# H08R6.net
KiCad netlist of a schematic drawn in EAGLE
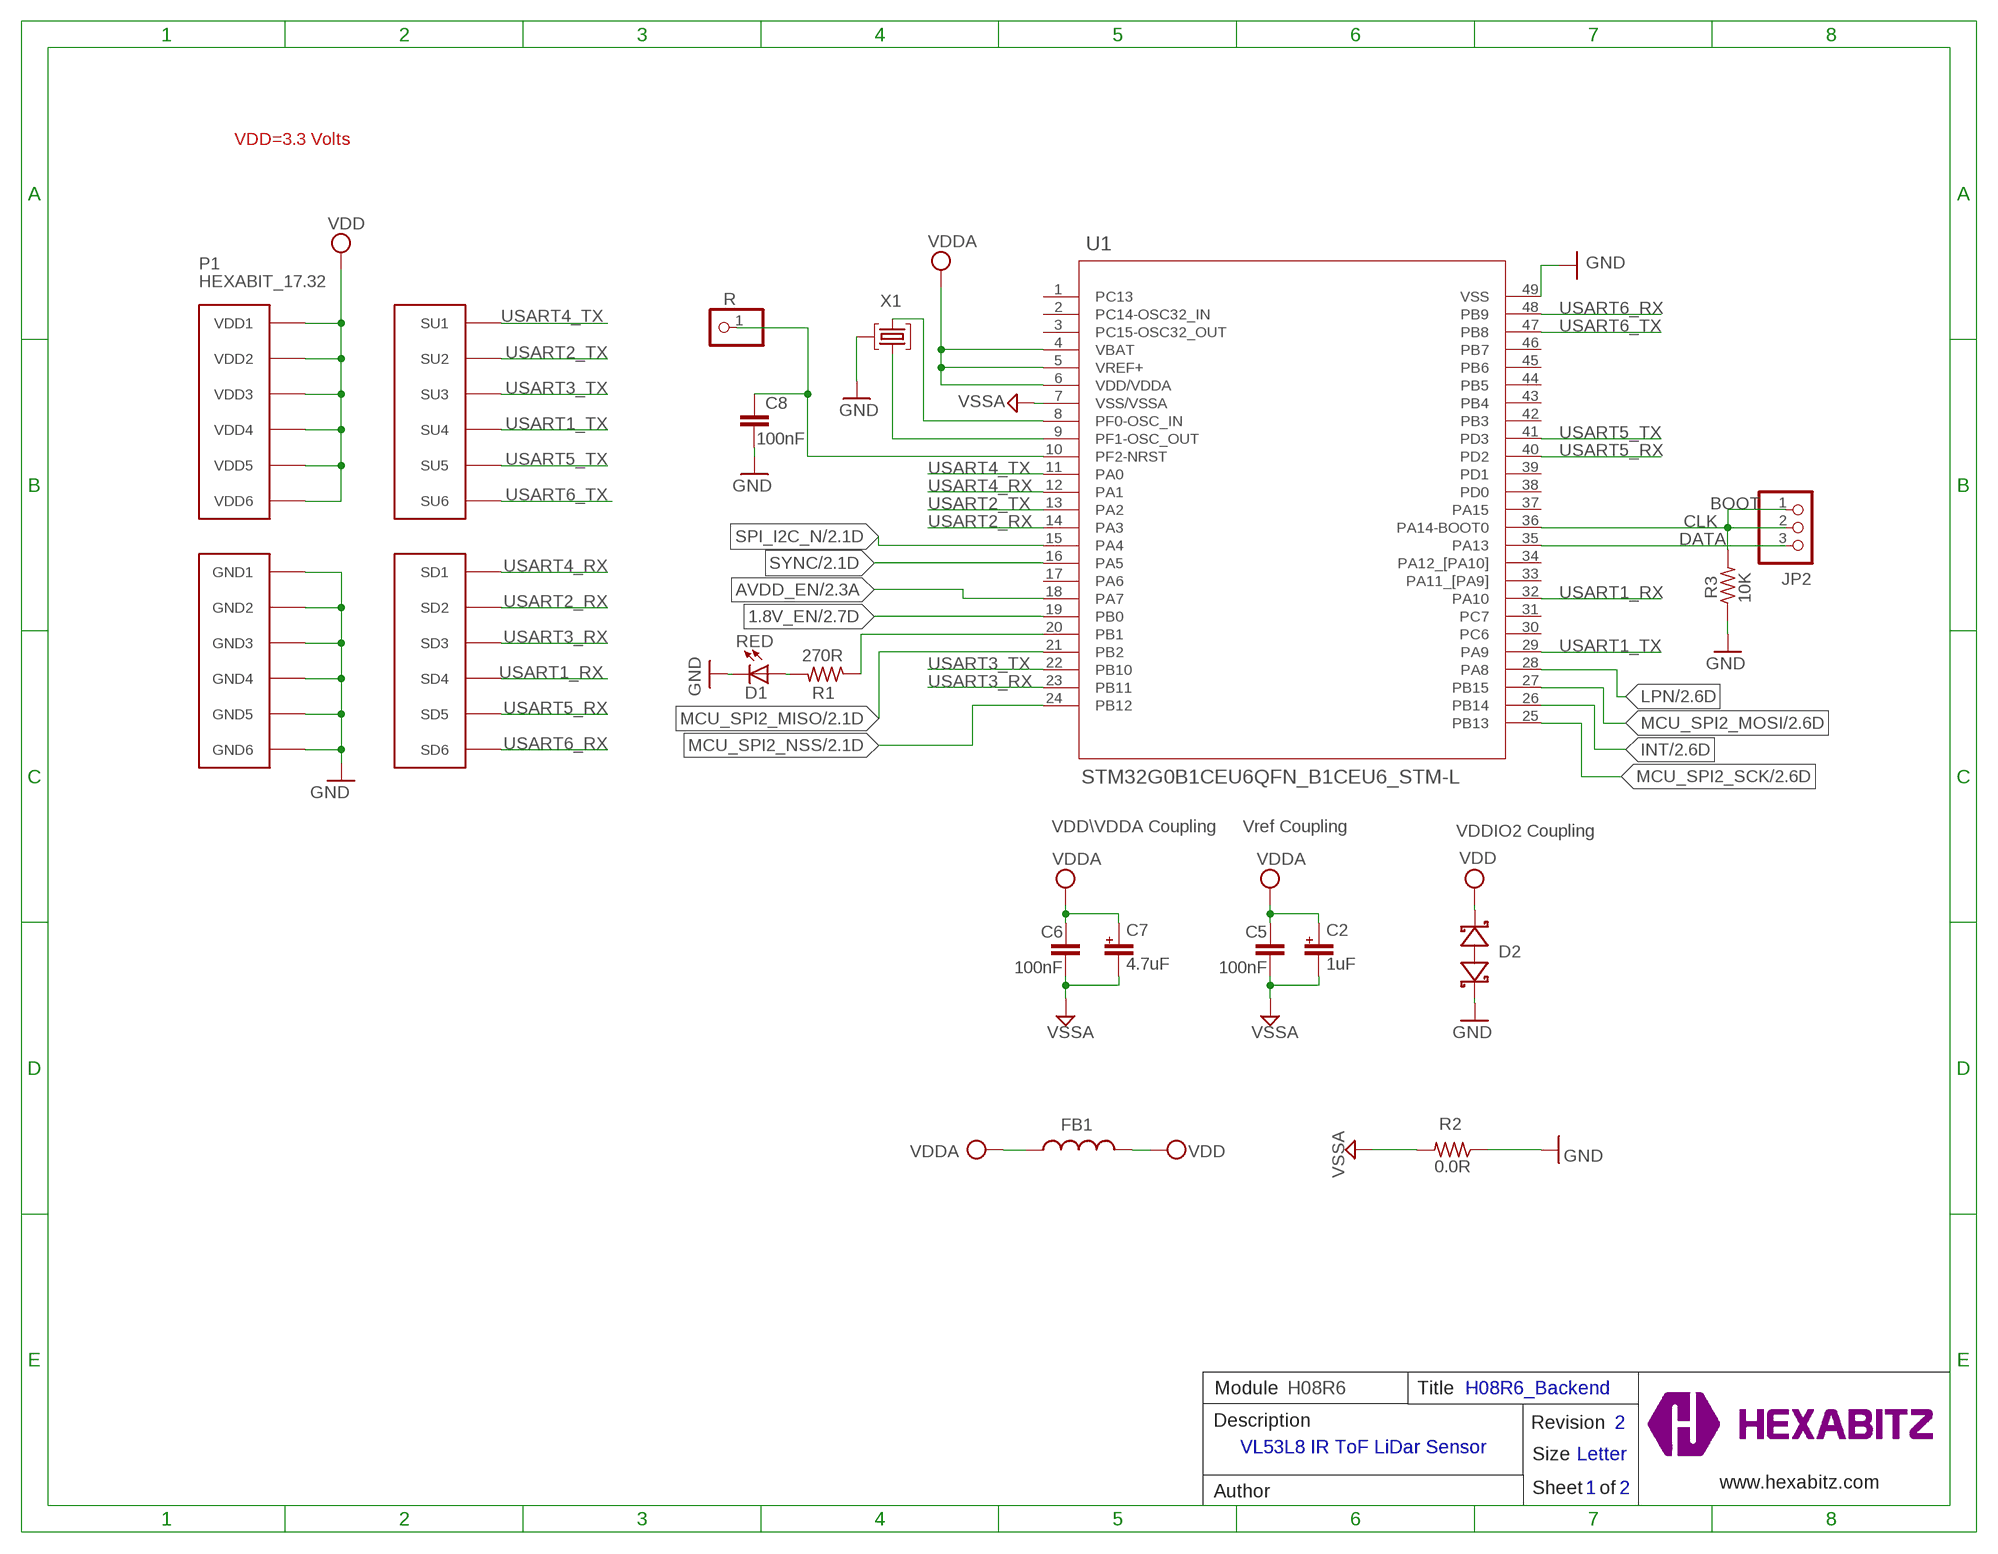
[diagram p0: schematic, sheet 1]
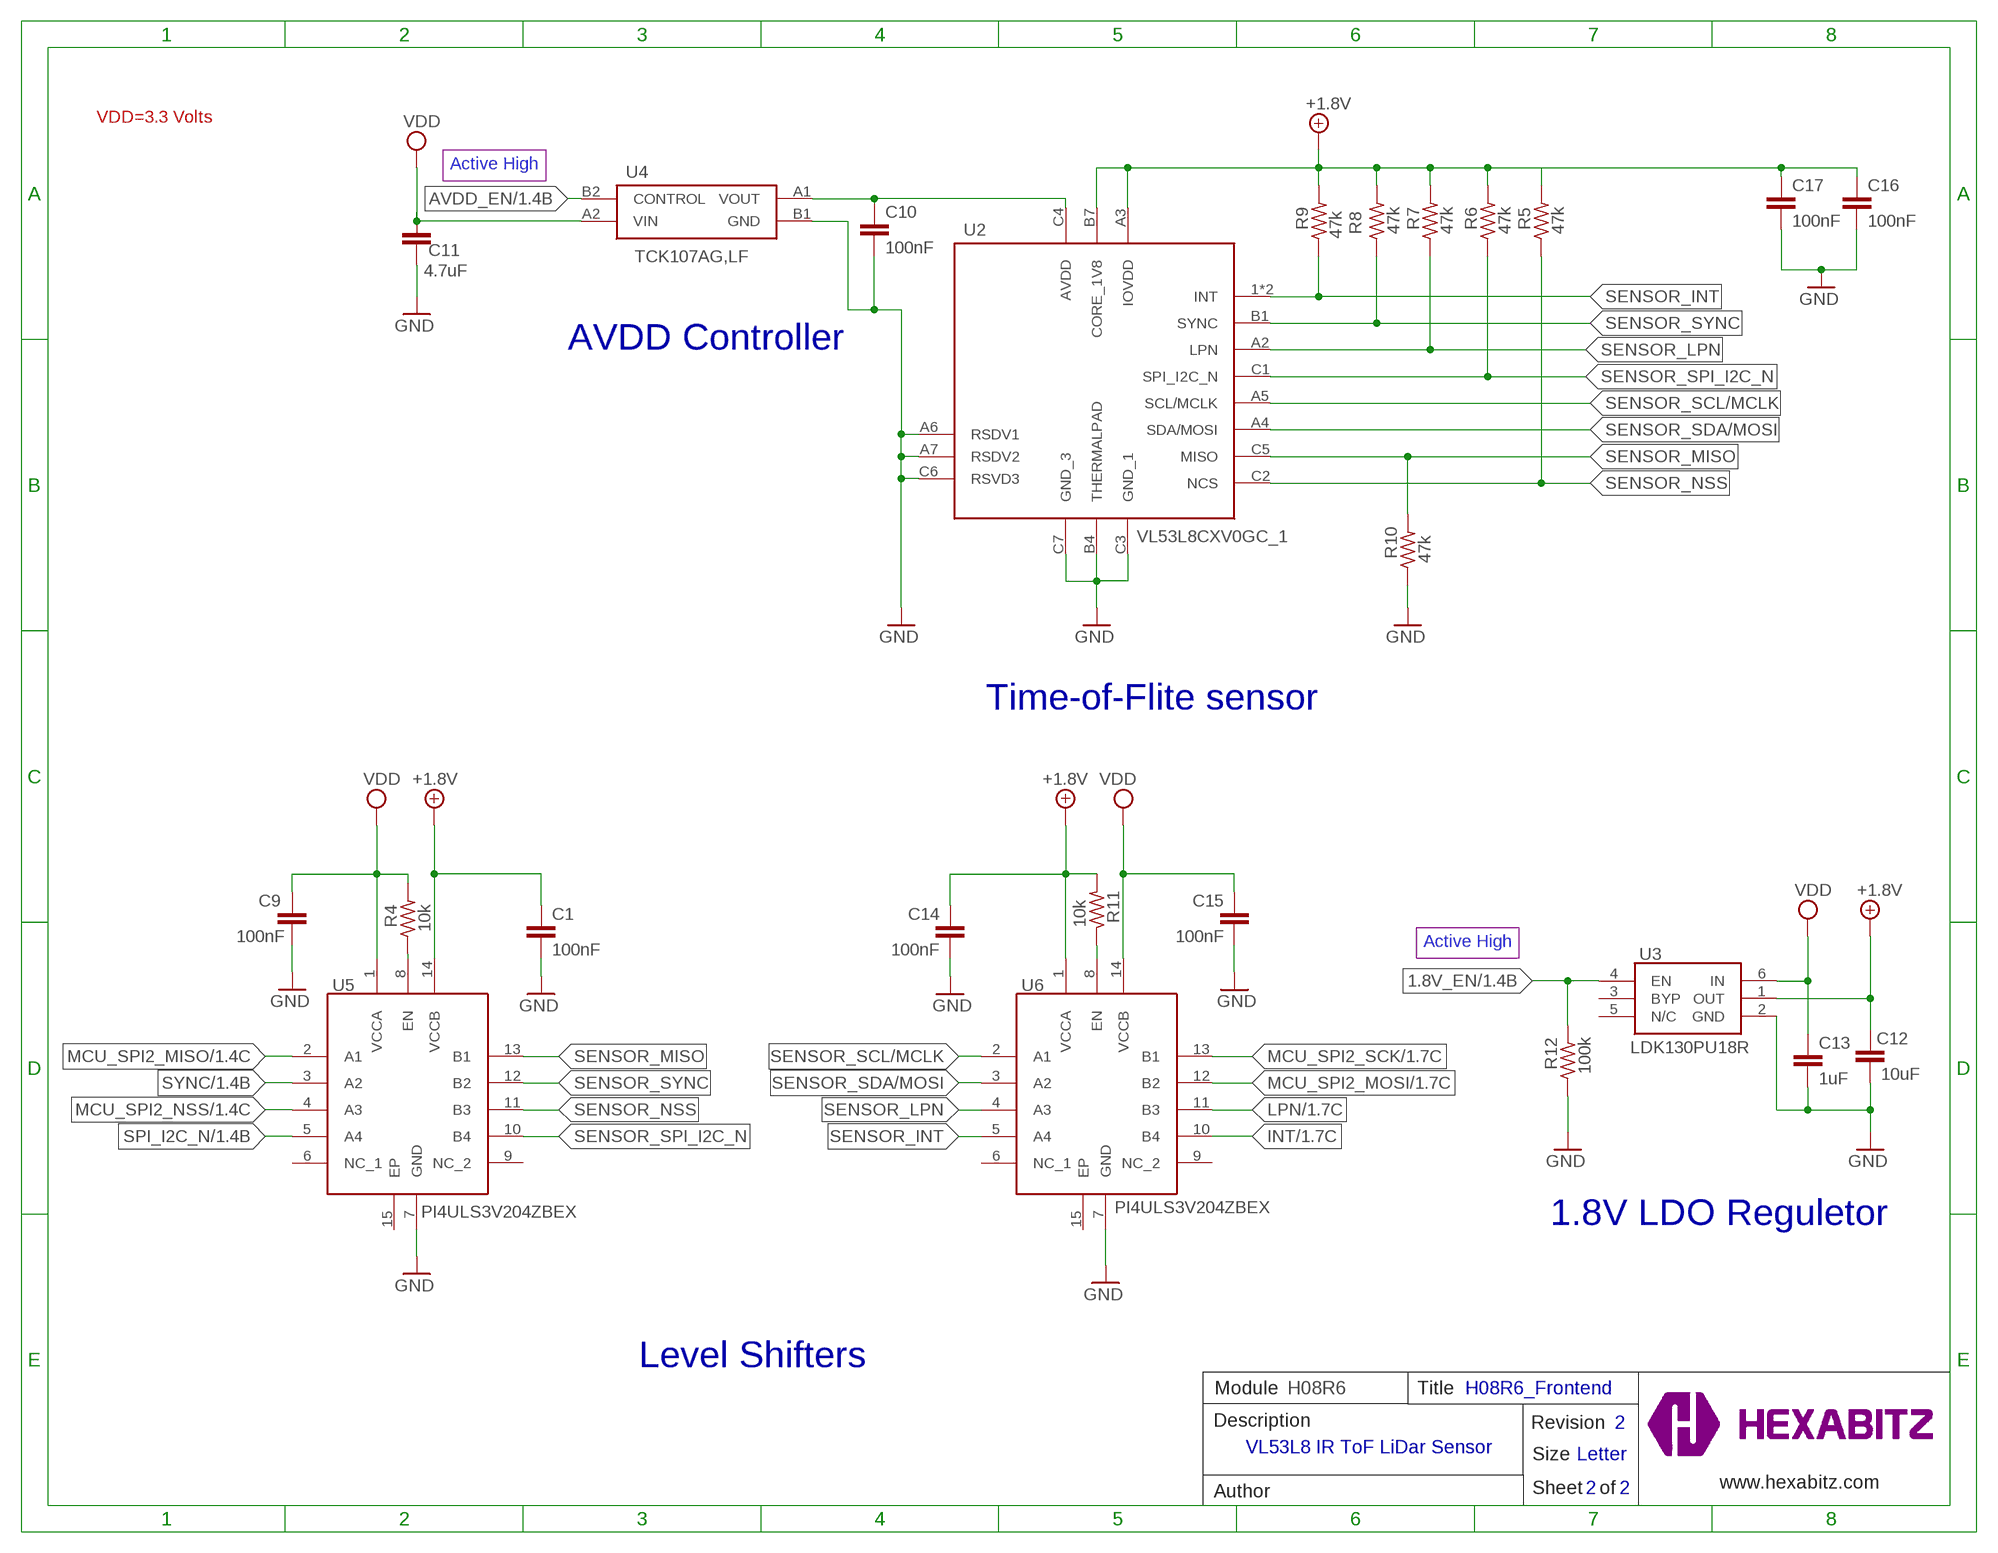
[diagram p1: schematic, sheet 2]

(export (version "E")
  (design (tool "Eeschema 10.0.6"))
  (components
    (comp (ref "C2")
      (value "1uF")
      (footprint "eagle-import:C-0603-POL")
      (libsource (lib "eagle-import") (part "C-0603-POL"))
    )
    (comp (ref "C5")
      (value "100nF")
      (footprint "eagle-import:C-0402")
      (libsource (lib "eagle-import") (part "C-0402"))
    )
    (comp (ref "C6")
      (value "100nF")
      (footprint "eagle-import:C-0402")
      (libsource (lib "eagle-import") (part "C-0402"))
    )
    (comp (ref "C7")
      (value "4.7uF")
      (footprint "eagle-import:C-0603-POL")
      (libsource (lib "eagle-import") (part "C-0603-POL"))
    )
    (comp (ref "C8")
      (value "100nF")
      (footprint "eagle-import:C-0402")
      (libsource (lib "eagle-import") (part "C-0402"))
    )
    (comp (ref "D1")
      (value "RED")
      (footprint "eagle-import:VLMS1300-GS08")
      (fields
        (field (name "MPN") "VLMS1300-GS08")
        (field (name "MFN") "Vishay")
        (field (name "MPN_1") "VLMS1300-GS08")
        (field (name "OCTOPART_URL") "https://octopart.com/vlms1300-gs08-vishay-21709201?r=sp&s=_gcP4_q8T1SC6PJQPTQ9yA")
      )
      (libsource (lib "eagle-import") (part "VLMS1300-GS08"))
    )
    (comp (ref "D2")
      (value "BOURNS_CDSOD323-T03SCBOURNS_CDSOD323-T03SC_0_0")
      (footprint "eagle-import:BOURNS_CDSOD323-T03SC_0")
      (fields (field (name "MPN") "CDSOD323-T03SC"))
      (libsource (lib "eagle-import") (part "BOURNS_CDSOD323-T03SCBOURNS_CDSOD323-T03SC_0_0"))
    )
    (comp (ref "FB1")
      (value "FB-TDK_MMZ1608Y300B")
      (footprint "eagle-import:FB-TDK_MMZ1608Y300B")
      (fields
        (field (name "MFN") "TDK ")
        (field (name "MPN") "MMZ1608Y300B")
        (field (name "OCTOPART_URL") "https://octopart.com/mmz1608y300b-tdk-368280?r=sp&s=cd9_2ZEqQ9q9UNBuQgHAiA")
      )
      (libsource (lib "eagle-import") (part "FB-TDK_MMZ1608Y300B"))
    )
    (comp (ref "JP2")
      (value "PINHD-1X3")
      (footprint "eagle-import:1X03")
      (libsource (lib "eagle-import") (part "PINHD-1X3"))
    )
    (comp (ref "P1")
      (value "HEXABIT_17.32")
      (footprint "eagle-import:HEXABIT_17.32")
      (libsource (lib "eagle-import") (part "HEXABIT_?17.32"))
    )
    (comp (ref "R")
      (value "R")
      (footprint "eagle-import:1X01")
      (fields (field (name "MPN") "87227-1"))
      (libsource (lib "eagle-import") (part "PINHD-1X1"))
    )
    (comp (ref "R1")
      (value "270R")
      (footprint "eagle-import:R-0402")
      (libsource (lib "eagle-import") (part "R-0402"))
    )
    (comp (ref "R2")
      (value "0.0R")
      (footprint "eagle-import:R-0402")
      (fields
        (field (name "MFN") "Yageo")
        (field (name "MPN") "RC0603JR-070RL")
        (field (name "OCTOPART_URL") "https://octopart.com/rc0603jr-070rl-yageo-1241539?r=sp&s=X2NteqRjRNWrnx42Y0aliA")
        (field (name "RESISTANCE") "0.0 Ohm")
      )
      (libsource (lib "eagle-import") (part "R-0402"))
    )
    (comp (ref "R3")
      (value "10K")
      (footprint "eagle-import:R-0402")
      (libsource (lib "eagle-import") (part "R-0402"))
    )
    (comp (ref "TRIMBLE-LOGO1")
      (value "HEXA-LOGO")
      (footprint "eagle-import:HEXA-LOGO")
      (libsource (lib "eagle-import") (part "HEXA-LOGO"))
    )
    (comp (ref "U1")
      (value "STM32G0B1CEU6QFN_B1CEU6_STM-L")
      (footprint "eagle-import:QFN_B1CEU6_STM-L")
      (fields
        (field (name "MANUFACTURER_PART_NUMBER") "STM32G0B1CEU6")
        (field (name "COPYRIGHT") "Copyright (C) 2021 Ultra Librarian. All rights reserved.")
      )
      (libsource (lib "eagle-import") (part "STM32G0B1CEU6QFN_B1CEU6_STM-L"))
    )
    (comp (ref "X1")
      (value "XTALL_CSTCE8M00G52")
      (footprint "eagle-import:XTALL_CSTCE8M00G52")
      (fields (field (name "MPN") "CSTCE8M00G52Z-R0"))
      (libsource (lib "eagle-import") (part "XTALL_CSTCE8M00G52"))
    )
    (comp (ref "C1")
      (value "100nF")
      (footprint "eagle-import:C-0402")
      (libsource (lib "eagle-import") (part "C-0402"))
    )
    (comp (ref "C9")
      (value "100nF")
      (footprint "eagle-import:C-0402")
      (libsource (lib "eagle-import") (part "C-0402"))
    )
    (comp (ref "C10")
      (value "100nF")
      (footprint "eagle-import:C-0402")
      (libsource (lib "eagle-import") (part "C-0402"))
    )
    (comp (ref "C11")
      (value "4.7uF")
      (footprint "eagle-import:C-0603")
      (libsource (lib "eagle-import") (part "C-0603"))
    )
    (comp (ref "C12")
      (value "10uF")
      (footprint "eagle-import:C-0402")
      (libsource (lib "eagle-import") (part "C-0402"))
    )
    (comp (ref "C13")
      (value "1uF")
      (footprint "eagle-import:C-0402")
      (libsource (lib "eagle-import") (part "C-0402"))
    )
    (comp (ref "C14")
      (value "100nF")
      (footprint "eagle-import:C-0402")
      (libsource (lib "eagle-import") (part "C-0402"))
    )
    (comp (ref "C15")
      (value "100nF")
      (footprint "eagle-import:C-0402")
      (libsource (lib "eagle-import") (part "C-0402"))
    )
    (comp (ref "C16")
      (value "100nF")
      (footprint "eagle-import:C-0402")
      (libsource (lib "eagle-import") (part "C-0402"))
    )
    (comp (ref "C17")
      (value "100nF")
      (footprint "eagle-import:C-0402")
      (libsource (lib "eagle-import") (part "C-0402"))
    )
    (comp (ref "R4")
      (value "10k")
      (footprint "eagle-import:R-0402")
      (libsource (lib "eagle-import") (part "R-0402"))
    )
    (comp (ref "R5")
      (value "47k")
      (footprint "eagle-import:R-0402")
      (libsource (lib "eagle-import") (part "R-0402"))
    )
    (comp (ref "R6")
      (value "47k")
      (footprint "eagle-import:R-0402")
      (libsource (lib "eagle-import") (part "R-0402"))
    )
    (comp (ref "R7")
      (value "47k")
      (footprint "eagle-import:R-0402")
      (libsource (lib "eagle-import") (part "R-0402"))
    )
    (comp (ref "R8")
      (value "47k")
      (footprint "eagle-import:R-0402")
      (libsource (lib "eagle-import") (part "R-0402"))
    )
    (comp (ref "R9")
      (value "47k")
      (footprint "eagle-import:R-0402")
      (libsource (lib "eagle-import") (part "R-0402"))
    )
    (comp (ref "R10")
      (value "47k")
      (footprint "eagle-import:R-0402")
      (libsource (lib "eagle-import") (part "R-0402"))
    )
    (comp (ref "R11")
      (value "10k")
      (footprint "eagle-import:R-0402")
      (libsource (lib "eagle-import") (part "R-0402"))
    )
    (comp (ref "R12")
      (value "100k")
      (footprint "eagle-import:R-0402")
      (libsource (lib "eagle-import") (part "R-0402"))
    )
    (comp (ref "U2")
      (value "VL53L8CXV0GC_1")
      (footprint "eagle-import:VL53L8CXV0GC1")
      (fields
        (field (name "ARROW_PART_NUMBER") "VL53L8CXV0GC/1")
        (field (name "MOUSER_PART_NUMBER") "511-VL53L8CXV0GC/1")
      )
      (libsource (lib "eagle-import") (part "VL53L8CXV0GC_1"))
    )
    (comp (ref "U3")
      (value "LDK130PU18R")
      (footprint "eagle-import:LDK130PU18R")
      (fields (field (name "MOUSER_PART_NUMBER") "511-LDK130PU18R"))
      (libsource (lib "eagle-import") (part "LDK130PU18R"))
    )
    (comp (ref "U4")
      (value "TCK107AG,LF")
      (footprint "eagle-import:BGA4C40P2X2_79X79X59")
      (fields (field (name "MOUSER_PART_NUMBER") "757-TCK107AGLF"))
      (libsource (lib "eagle-import") (part "TCK107AG,LF"))
    )
    (comp (ref "U5")
      (value "PI4ULS3V204ZBEX")
      (footprint "eagle-import:PI4ULS3V204ZBEX")
      (fields (field (name "MOUSER_PART_NUMBER") "729-PI4ULS3V204ZBEX"))
      (libsource (lib "eagle-import") (part "PI4ULS3V204ZBEX"))
    )
    (comp (ref "U6")
      (value "PI4ULS3V204ZBEX")
      (footprint "eagle-import:PI4ULS3V204ZBEX")
      (fields (field (name "MOUSER_PART_NUMBER") "729-PI4ULS3V204ZBEX"))
      (libsource (lib "eagle-import") (part "PI4ULS3V204ZBEX"))
    )
  )
  (nets
    (net (code "1") (name "+1.8V") (class "Default")
      (node (ref "C1") (pin "1") (pinfunction "1_1") (pintype "passive"))
      (node (ref "C12") (pin "1") (pinfunction "1_1") (pintype "passive"))
      (node (ref "C14") (pin "1") (pinfunction "1_1") (pintype "passive"))
      (node (ref "C16") (pin "1") (pinfunction "1_1") (pintype "passive"))
      (node (ref "C17") (pin "1") (pinfunction "1_1") (pintype "passive"))
      (node (ref "R11") (pin "2") (pinfunction "2_2") (pintype "passive"))
      (node (ref "R5") (pin "2") (pinfunction "2_2") (pintype "passive"))
      (node (ref "R6") (pin "2") (pinfunction "2_2") (pintype "passive"))
      (node (ref "R7") (pin "2") (pinfunction "2_2") (pintype "passive"))
      (node (ref "R8") (pin "2") (pinfunction "2_2") (pintype "passive"))
      (node (ref "R9") (pin "2") (pinfunction "2_2") (pintype "passive"))
      (node (ref "U2") (pin "A3") (pinfunction "IOVDD_A3") (pintype "bidirectional"))
      (node (ref "U2") (pin "B7") (pinfunction "CORE_1V8_B7") (pintype "bidirectional"))
      (node (ref "U3") (pin "1") (pinfunction "OUT_1") (pintype "bidirectional"))
      (node (ref "U5") (pin "14") (pinfunction "VCCB_14") (pintype "bidirectional"))
      (node (ref "U6") (pin "1") (pinfunction "VCCA_1") (pintype "bidirectional"))
    )
    (net (code "2") (name "1.8V_EN") (class "Default")
      (node (ref "R12") (pin "2") (pinfunction "2_2") (pintype "passive"))
      (node (ref "U1") (pin "19") (pinfunction "PB0_19") (pintype "bidirectional"))
      (node (ref "U3") (pin "4") (pinfunction "EN_4") (pintype "bidirectional"))
    )
    (net (code "3") (name "AVDD_EN") (class "Default")
      (node (ref "U1") (pin "18") (pinfunction "PA7_18") (pintype "bidirectional"))
      (node (ref "U4") (pin "B2") (pinfunction "CONTROL_B2") (pintype "bidirectional"))
    )
    (net (code "4") (name "CLK") (class "Default")
      (node (ref "JP2") (pin "1") (pinfunction "1_1") (pintype "passive"))
      (node (ref "JP2") (pin "2") (pinfunction "2_2") (pintype "passive"))
      (node (ref "R3") (pin "2") (pinfunction "2_2") (pintype "passive"))
      (node (ref "U1") (pin "36") (pinfunction "PA14-BOOT0_36") (pintype "bidirectional"))
    )
    (net (code "5") (name "DATA") (class "Default")
      (node (ref "JP2") (pin "3") (pinfunction "3_3") (pintype "passive"))
      (node (ref "U1") (pin "35") (pinfunction "PA13_35") (pintype "bidirectional"))
    )
    (net (code "6") (name "GND") (class "Default")
      (node (ref "C1") (pin "2") (pinfunction "2_2") (pintype "passive"))
      (node (ref "C10") (pin "2") (pinfunction "2_2") (pintype "passive"))
      (node (ref "C11") (pin "2") (pinfunction "2_2") (pintype "passive"))
      (node (ref "C12") (pin "2") (pinfunction "2_2") (pintype "passive"))
      (node (ref "C13") (pin "2") (pinfunction "2_2") (pintype "passive"))
      (node (ref "C14") (pin "2") (pinfunction "2_2") (pintype "passive"))
      (node (ref "C15") (pin "2") (pinfunction "2_2") (pintype "passive"))
      (node (ref "C16") (pin "2") (pinfunction "2_2") (pintype "passive"))
      (node (ref "C17") (pin "2") (pinfunction "2_2") (pintype "passive"))
      (node (ref "C8") (pin "2") (pinfunction "2_2") (pintype "passive"))
      (node (ref "C9") (pin "2") (pinfunction "2_2") (pintype "passive"))
      (node (ref "D1") (pin "C") (pinfunction "C_C") (pintype "passive"))
      (node (ref "D2") (pin "2") (pinfunction "C_2") (pintype "passive"))
      (node (ref "P1") (pin "PAD_PD10") (pinfunction "GND4_PAD_PD10") (pintype "power_in"))
      (node (ref "P1") (pin "PAD_PD11") (pinfunction "GND5_PAD_PD11") (pintype "power_in"))
      (node (ref "P1") (pin "PAD_PD12") (pinfunction "GND6_PAD_PD12") (pintype "power_in"))
      (node (ref "P1") (pin "PAD_PD7") (pinfunction "GND1_PAD_PD7") (pintype "power_in"))
      (node (ref "P1") (pin "PAD_PD8") (pinfunction "GND2_PAD_PD8") (pintype "power_in"))
      (node (ref "P1") (pin "PAD_PD9") (pinfunction "GND3_PAD_PD9") (pintype "power_in"))
      (node (ref "R10") (pin "1") (pinfunction "1_1") (pintype "passive"))
      (node (ref "R12") (pin "1") (pinfunction "1_1") (pintype "passive"))
      (node (ref "R2") (pin "1") (pinfunction "1_1") (pintype "passive"))
      (node (ref "R3") (pin "1") (pinfunction "1_1") (pintype "passive"))
      (node (ref "U1") (pin "49") (pinfunction "VSS_49") (pintype "passive"))
      (node (ref "U2") (pin "A6") (pinfunction "RSDV1_A6") (pintype "bidirectional"))
      (node (ref "U2") (pin "A7") (pinfunction "RSDV2_A7") (pintype "bidirectional"))
      (node (ref "U2") (pin "B4") (pinfunction "THERMALPAD_B4") (pintype "bidirectional"))
      (node (ref "U2") (pin "C3") (pinfunction "GND_1_C3") (pintype "bidirectional"))
      (node (ref "U2") (pin "C6") (pinfunction "RSVD3_C6") (pintype "bidirectional"))
      (node (ref "U2") (pin "C7") (pinfunction "GND_3_C7") (pintype "bidirectional"))
      (node (ref "U3") (pin "2") (pinfunction "GND_2") (pintype "bidirectional"))
      (node (ref "U4") (pin "B1") (pinfunction "GND_B1") (pintype "bidirectional"))
      (node (ref "U5") (pin "7") (pinfunction "GND_7") (pintype "bidirectional"))
      (node (ref "U6") (pin "7") (pinfunction "GND_7") (pintype "bidirectional"))
      (node (ref "X1") (pin "P$2") (pinfunction "2_P$2") (pintype "passive"))
    )
    (net (code "7") (name "INT") (class "Default")
      (node (ref "U1") (pin "26") (pinfunction "PB14_26") (pintype "bidirectional"))
      (node (ref "U6") (pin "10") (pinfunction "B4_10") (pintype "bidirectional"))
    )
    (net (code "8") (name "LPN") (class "Default")
      (node (ref "U1") (pin "28") (pinfunction "PA8_28") (pintype "bidirectional"))
      (node (ref "U6") (pin "11") (pinfunction "B3_11") (pintype "bidirectional"))
    )
    (net (code "9") (name "MCU_SPI2_MISO") (class "Default")
      (node (ref "U1") (pin "21") (pinfunction "PB2_21") (pintype "bidirectional"))
      (node (ref "U5") (pin "2") (pinfunction "A1_2") (pintype "bidirectional"))
    )
    (net (code "10") (name "MCU_SPI2_MOSI") (class "Default")
      (node (ref "U1") (pin "27") (pinfunction "PB15_27") (pintype "bidirectional"))
      (node (ref "U6") (pin "12") (pinfunction "B2_12") (pintype "bidirectional"))
    )
    (net (code "11") (name "MCU_SPI2_NSS") (class "Default")
      (node (ref "U1") (pin "24") (pinfunction "PB12_24") (pintype "bidirectional"))
      (node (ref "U5") (pin "4") (pinfunction "A3_4") (pintype "bidirectional"))
    )
    (net (code "12") (name "MCU_SPI2_SCK") (class "Default")
      (node (ref "U1") (pin "25") (pinfunction "PB13_25") (pintype "bidirectional"))
      (node (ref "U6") (pin "13") (pinfunction "B1_13") (pintype "bidirectional"))
    )
    (net (code "13") (name "Net-(D1-PadA)") (class "Default")
      (node (ref "D1") (pin "A") (pinfunction "A_A") (pintype "passive"))
      (node (ref "R1") (pin "2") (pinfunction "2_2") (pintype "passive"))
    )
    (net (code "14") (name "Net-(U1-PB1)") (class "Default")
      (node (ref "R1") (pin "1") (pinfunction "1_1") (pintype "passive"))
      (node (ref "U1") (pin "20") (pinfunction "PB1_20") (pintype "bidirectional"))
    )
    (net (code "15") (name "Net-(U1-PF0-OSC_IN)") (class "Default")
      (node (ref "U1") (pin "8") (pinfunction "PF0-OSC_IN_8") (pintype "bidirectional"))
      (node (ref "X1") (pin "P$3") (pinfunction "3_P$3") (pintype "passive"))
    )
    (net (code "16") (name "Net-(U1-PF1-OSC_OUT)") (class "Default")
      (node (ref "U1") (pin "9") (pinfunction "PF1-OSC_OUT_9") (pintype "output"))
      (node (ref "X1") (pin "P$1") (pinfunction "1_P$1") (pintype "passive"))
    )
    (net (code "17") (name "Net-(U1-PF2-NRST)") (class "Default")
      (node (ref "C8") (pin "1") (pinfunction "1_1") (pintype "passive"))
      (node (ref "R") (pin "1") (pinfunction "1_1") (pintype "passive"))
      (node (ref "U1") (pin "10") (pinfunction "PF2-NRST_10") (pintype "bidirectional"))
    )
    (net (code "18") (name "Net-(U2-AVDD)") (class "Default")
      (node (ref "C10") (pin "1") (pinfunction "1_1") (pintype "passive"))
      (node (ref "U2") (pin "C4") (pinfunction "AVDD_C4") (pintype "bidirectional"))
      (node (ref "U4") (pin "A1") (pinfunction "VOUT_A1") (pintype "bidirectional"))
    )
    (net (code "19") (name "Net-(U5-EN)") (class "Default")
      (node (ref "R4") (pin "1") (pinfunction "1_1") (pintype "passive"))
      (node (ref "U5") (pin "8") (pinfunction "EN_8") (pintype "bidirectional"))
    )
    (net (code "20") (name "Net-(U6-EN)") (class "Default")
      (node (ref "R11") (pin "1") (pinfunction "1_1") (pintype "passive"))
      (node (ref "U6") (pin "8") (pinfunction "EN_8") (pintype "bidirectional"))
    )
    (net (code "21") (name "SENSOR_INT") (class "Default")
      (node (ref "R9") (pin "1") (pinfunction "1_1") (pintype "passive"))
      (node (ref "U2") (pin "1") (pinfunction "INT_1") (pintype "bidirectional"))
      (node (ref "U2") (pin "A1") (pinfunction "INT_A1") (pintype "bidirectional"))
      (node (ref "U6") (pin "5") (pinfunction "A4_5") (pintype "bidirectional"))
    )
    (net (code "22") (name "SENSOR_LPN") (class "Default")
      (node (ref "R7") (pin "1") (pinfunction "1_1") (pintype "passive"))
      (node (ref "U2") (pin "A2") (pinfunction "LPN_A2") (pintype "bidirectional"))
      (node (ref "U6") (pin "4") (pinfunction "A3_4") (pintype "bidirectional"))
    )
    (net (code "23") (name "SENSOR_MISO") (class "Default")
      (node (ref "R10") (pin "2") (pinfunction "2_2") (pintype "passive"))
      (node (ref "U2") (pin "C5") (pinfunction "MISO_C5") (pintype "bidirectional"))
      (node (ref "U5") (pin "13") (pinfunction "B1_13") (pintype "bidirectional"))
    )
    (net (code "24") (name "SENSOR_NSS") (class "Default")
      (node (ref "R5") (pin "1") (pinfunction "1_1") (pintype "passive"))
      (node (ref "U2") (pin "C2") (pinfunction "NCS_C2") (pintype "bidirectional"))
      (node (ref "U5") (pin "11") (pinfunction "B3_11") (pintype "bidirectional"))
    )
    (net (code "25") (name "SENSOR_SCL{slash}MCLK") (class "Default")
      (node (ref "U2") (pin "A5") (pinfunction "SCL/MCLK_A5") (pintype "bidirectional"))
      (node (ref "U6") (pin "2") (pinfunction "A1_2") (pintype "bidirectional"))
    )
    (net (code "26") (name "SENSOR_SDA{slash}MOSI") (class "Default")
      (node (ref "U2") (pin "A4") (pinfunction "SDA/MOSI_A4") (pintype "bidirectional"))
      (node (ref "U6") (pin "3") (pinfunction "A2_3") (pintype "bidirectional"))
    )
    (net (code "27") (name "SENSOR_SPI_I2C_N") (class "Default")
      (node (ref "R6") (pin "1") (pinfunction "1_1") (pintype "passive"))
      (node (ref "U2") (pin "C1") (pinfunction "SPI_I2C_N_C1") (pintype "bidirectional"))
      (node (ref "U5") (pin "10") (pinfunction "B4_10") (pintype "bidirectional"))
    )
    (net (code "28") (name "SENSOR_SYNC") (class "Default")
      (node (ref "R8") (pin "1") (pinfunction "1_1") (pintype "passive"))
      (node (ref "U2") (pin "B1") (pinfunction "SYNC_B1") (pintype "bidirectional"))
      (node (ref "U5") (pin "12") (pinfunction "B2_12") (pintype "bidirectional"))
    )
    (net (code "29") (name "SPI_I2C_N") (class "Default")
      (node (ref "U1") (pin "15") (pinfunction "PA4_15") (pintype "bidirectional"))
      (node (ref "U5") (pin "5") (pinfunction "A4_5") (pintype "bidirectional"))
    )
    (net (code "30") (name "SYNC") (class "Default")
      (node (ref "U1") (pin "16") (pinfunction "PA5_16") (pintype "bidirectional"))
      (node (ref "U5") (pin "3") (pinfunction "A2_3") (pintype "bidirectional"))
    )
    (net (code "31") (name "USART1_RX") (class "Default")
      (node (ref "P1") (pin "PAD_PD4") (pinfunction "SD4_PAD_PD4") (pintype "bidirectional"))
      (node (ref "U1") (pin "32") (pinfunction "PA10_32") (pintype "bidirectional"))
    )
    (net (code "32") (name "USART1_TX") (class "Default")
      (node (ref "P1") (pin "PAD_PU4") (pinfunction "SU4_PAD_PU4") (pintype "bidirectional"))
      (node (ref "U1") (pin "29") (pinfunction "PA9_29") (pintype "bidirectional"))
    )
    (net (code "33") (name "USART2_RX") (class "Default")
      (node (ref "P1") (pin "PAD_PD2") (pinfunction "SD2_PAD_PD2") (pintype "bidirectional"))
      (node (ref "U1") (pin "14") (pinfunction "PA3_14") (pintype "bidirectional"))
    )
    (net (code "34") (name "USART2_TX") (class "Default")
      (node (ref "P1") (pin "PAD_PU2") (pinfunction "SU2_PAD_PU2") (pintype "bidirectional"))
      (node (ref "U1") (pin "13") (pinfunction "PA2_13") (pintype "bidirectional"))
    )
    (net (code "35") (name "USART3_RX") (class "Default")
      (node (ref "P1") (pin "PAD_PD3") (pinfunction "SD3_PAD_PD3") (pintype "bidirectional"))
      (node (ref "U1") (pin "23") (pinfunction "PB11_23") (pintype "bidirectional"))
    )
    (net (code "36") (name "USART3_TX") (class "Default")
      (node (ref "P1") (pin "PAD_PU3") (pinfunction "SU3_PAD_PU3") (pintype "bidirectional"))
      (node (ref "U1") (pin "22") (pinfunction "PB10_22") (pintype "bidirectional"))
    )
    (net (code "37") (name "USART4_RX") (class "Default")
      (node (ref "P1") (pin "PAD_PD1") (pinfunction "SD1_PAD_PD1") (pintype "bidirectional"))
      (node (ref "U1") (pin "12") (pinfunction "PA1_12") (pintype "bidirectional"))
    )
    (net (code "38") (name "USART4_TX") (class "Default")
      (node (ref "P1") (pin "PAD_PU1") (pinfunction "SU1_PAD_PU1") (pintype "bidirectional"))
      (node (ref "U1") (pin "11") (pinfunction "PA0_11") (pintype "bidirectional"))
    )
    (net (code "39") (name "USART5_RX") (class "Default")
      (node (ref "P1") (pin "PAD_PD5") (pinfunction "SD5_PAD_PD5") (pintype "bidirectional"))
      (node (ref "U1") (pin "40") (pinfunction "PD2_40") (pintype "bidirectional"))
    )
    (net (code "40") (name "USART5_TX") (class "Default")
      (node (ref "P1") (pin "PAD_PU5") (pinfunction "SU5_PAD_PU5") (pintype "bidirectional"))
      (node (ref "U1") (pin "41") (pinfunction "PD3_41") (pintype "bidirectional"))
    )
    (net (code "41") (name "USART6_RX") (class "Default")
      (node (ref "P1") (pin "PAD_PD6") (pinfunction "SD6_PAD_PD6") (pintype "bidirectional"))
      (node (ref "U1") (pin "48") (pinfunction "PB9_48") (pintype "bidirectional"))
    )
    (net (code "42") (name "USART6_TX") (class "Default")
      (node (ref "P1") (pin "PAD_PU6") (pinfunction "SU6_PAD_PU6") (pintype "bidirectional"))
      (node (ref "U1") (pin "47") (pinfunction "PB8_47") (pintype "bidirectional"))
    )
    (net (code "43") (name "VDD") (class "Default")
      (node (ref "C11") (pin "1") (pinfunction "1_1") (pintype "passive"))
      (node (ref "C13") (pin "1") (pinfunction "1_1") (pintype "passive"))
      (node (ref "C15") (pin "1") (pinfunction "1_1") (pintype "passive"))
      (node (ref "C9") (pin "1") (pinfunction "1_1") (pintype "passive"))
      (node (ref "D2") (pin "1") (pinfunction "A_1") (pintype "passive"))
      (node (ref "FB1") (pin "2") (pinfunction "2_2") (pintype "passive"))
      (node (ref "P1") (pin "PAD_PU10") (pinfunction "VDD4_PAD_PU10") (pintype "power_in"))
      (node (ref "P1") (pin "PAD_PU11") (pinfunction "VDD5_PAD_PU11") (pintype "power_in"))
      (node (ref "P1") (pin "PAD_PU12") (pinfunction "VDD6_PAD_PU12") (pintype "power_in"))
      (node (ref "P1") (pin "PAD_PU7") (pinfunction "VDD1_PAD_PU7") (pintype "power_in"))
      (node (ref "P1") (pin "PAD_PU8") (pinfunction "VDD2_PAD_PU8") (pintype "power_in"))
      (node (ref "P1") (pin "PAD_PU9") (pinfunction "VDD3_PAD_PU9") (pintype "power_in"))
      (node (ref "R4") (pin "2") (pinfunction "2_2") (pintype "passive"))
      (node (ref "U3") (pin "6") (pinfunction "IN_6") (pintype "bidirectional"))
      (node (ref "U4") (pin "A2") (pinfunction "VIN_A2") (pintype "bidirectional"))
      (node (ref "U5") (pin "1") (pinfunction "VCCA_1") (pintype "bidirectional"))
      (node (ref "U6") (pin "14") (pinfunction "VCCB_14") (pintype "bidirectional"))
    )
    (net (code "44") (name "VDDA") (class "Default")
      (node (ref "C2") (pin "1") (pinfunction "1_1") (pintype "passive"))
      (node (ref "C5") (pin "1") (pinfunction "1_1") (pintype "passive"))
      (node (ref "C6") (pin "1") (pinfunction "1_1") (pintype "passive"))
      (node (ref "C7") (pin "1") (pinfunction "1_1") (pintype "passive"))
      (node (ref "FB1") (pin "1") (pinfunction "1_1") (pintype "passive"))
      (node (ref "U1") (pin "4") (pinfunction "VBAT_4") (pintype "passive"))
      (node (ref "U1") (pin "5") (pinfunction "VREF+_5") (pintype "power_in"))
      (node (ref "U1") (pin "6") (pinfunction "VDD/VDDA_6") (pintype "power_in"))
    )
    (net (code "45") (name "VSSA") (class "Default")
      (node (ref "C2") (pin "2") (pinfunction "2_2") (pintype "passive"))
      (node (ref "C5") (pin "2") (pinfunction "2_2") (pintype "passive"))
      (node (ref "C6") (pin "2") (pinfunction "2_2") (pintype "passive"))
      (node (ref "C7") (pin "2") (pinfunction "2_2") (pintype "passive"))
      (node (ref "R2") (pin "2") (pinfunction "2_2") (pintype "passive"))
      (node (ref "U1") (pin "7") (pinfunction "VSS/VSSA_7") (pintype "passive"))
    )
    (net (code "46") (name "unconnected-(U1-PA6-Pad17)") (class "Default")
      (node (ref "U1") (pin "17") (pinfunction "PA6_17") (pintype "bidirectional"))
    )
    (net (code "47") (name "unconnected-(U1-PA11_[PA9]-Pad33)") (class "Default")
      (node (ref "U1") (pin "33") (pinfunction "PA11_[PA9]_33") (pintype "bidirectional"))
    )
    (net (code "48") (name "unconnected-(U1-PA12_[PA10]-Pad34)") (class "Default")
      (node (ref "U1") (pin "34") (pinfunction "PA12_[PA10]_34") (pintype "bidirectional"))
    )
    (net (code "49") (name "unconnected-(U1-PA15-Pad37)") (class "Default")
      (node (ref "U1") (pin "37") (pinfunction "PA15_37") (pintype "bidirectional"))
    )
    (net (code "50") (name "unconnected-(U1-PB3-Pad42)") (class "Default")
      (node (ref "U1") (pin "42") (pinfunction "PB3_42") (pintype "bidirectional"))
    )
    (net (code "51") (name "unconnected-(U1-PB4-Pad43)") (class "Default")
      (node (ref "U1") (pin "43") (pinfunction "PB4_43") (pintype "bidirectional"))
    )
    (net (code "52") (name "unconnected-(U1-PB5-Pad44)") (class "Default")
      (node (ref "U1") (pin "44") (pinfunction "PB5_44") (pintype "bidirectional"))
    )
    (net (code "53") (name "unconnected-(U1-PB6-Pad45)") (class "Default")
      (node (ref "U1") (pin "45") (pinfunction "PB6_45") (pintype "bidirectional"))
    )
    (net (code "54") (name "unconnected-(U1-PB7-Pad46)") (class "Default")
      (node (ref "U1") (pin "46") (pinfunction "PB7_46") (pintype "bidirectional"))
    )
    (net (code "55") (name "unconnected-(U1-PC6-Pad30)") (class "Default")
      (node (ref "U1") (pin "30") (pinfunction "PC6_30") (pintype "bidirectional"))
    )
    (net (code "56") (name "unconnected-(U1-PC7-Pad31)") (class "Default")
      (node (ref "U1") (pin "31") (pinfunction "PC7_31") (pintype "bidirectional"))
    )
    (net (code "57") (name "unconnected-(U1-PC13-Pad1)") (class "Default")
      (node (ref "U1") (pin "1") (pinfunction "PC13_1") (pintype "bidirectional"))
    )
    (net (code "58") (name "unconnected-(U1-PC14-OSC32_IN-Pad2)") (class "Default")
      (node (ref "U1") (pin "2") (pinfunction "PC14-OSC32_IN_2") (pintype "bidirectional"))
    )
    (net (code "59") (name "unconnected-(U1-PC15-OSC32_OUT-Pad3)") (class "Default")
      (node (ref "U1") (pin "3") (pinfunction "PC15-OSC32_OUT_3") (pintype "output"))
    )
    (net (code "60") (name "unconnected-(U1-PD0-Pad38)") (class "Default")
      (node (ref "U1") (pin "38") (pinfunction "PD0_38") (pintype "bidirectional"))
    )
    (net (code "61") (name "unconnected-(U1-PD1-Pad39)") (class "Default")
      (node (ref "U1") (pin "39") (pinfunction "PD1_39") (pintype "bidirectional"))
    )
    (net (code "62") (name "unconnected-(U3-BYP-Pad3)") (class "Default")
      (node (ref "U3") (pin "3") (pinfunction "BYP_3") (pintype "no_connect"))
    )
    (net (code "63") (name "unconnected-(U3-N{slash}C-Pad5)") (class "Default")
      (node (ref "U3") (pin "5") (pinfunction "N/C_5") (pintype "no_connect"))
    )
    (net (code "64") (name "unconnected-(U5-EP-Pad15)") (class "Default")
      (node (ref "U5") (pin "15") (pinfunction "EP_15") (pintype "no_connect"))
    )
    (net (code "65") (name "unconnected-(U5-NC_1-Pad6)") (class "Default")
      (node (ref "U5") (pin "6") (pinfunction "NC_1_6") (pintype "no_connect"))
    )
    (net (code "66") (name "unconnected-(U5-NC_2-Pad9)") (class "Default")
      (node (ref "U5") (pin "9") (pinfunction "NC_2_9") (pintype "no_connect"))
    )
    (net (code "67") (name "unconnected-(U6-EP-Pad15)") (class "Default")
      (node (ref "U6") (pin "15") (pinfunction "EP_15") (pintype "no_connect"))
    )
    (net (code "68") (name "unconnected-(U6-NC_1-Pad6)") (class "Default")
      (node (ref "U6") (pin "6") (pinfunction "NC_1_6") (pintype "no_connect"))
    )
    (net (code "69") (name "unconnected-(U6-NC_2-Pad9)") (class "Default")
      (node (ref "U6") (pin "9") (pinfunction "NC_2_9") (pintype "no_connect"))
    )
  )
)
